# attiny_bo.net
KiCad netlist of a schematic drawn in EAGLE
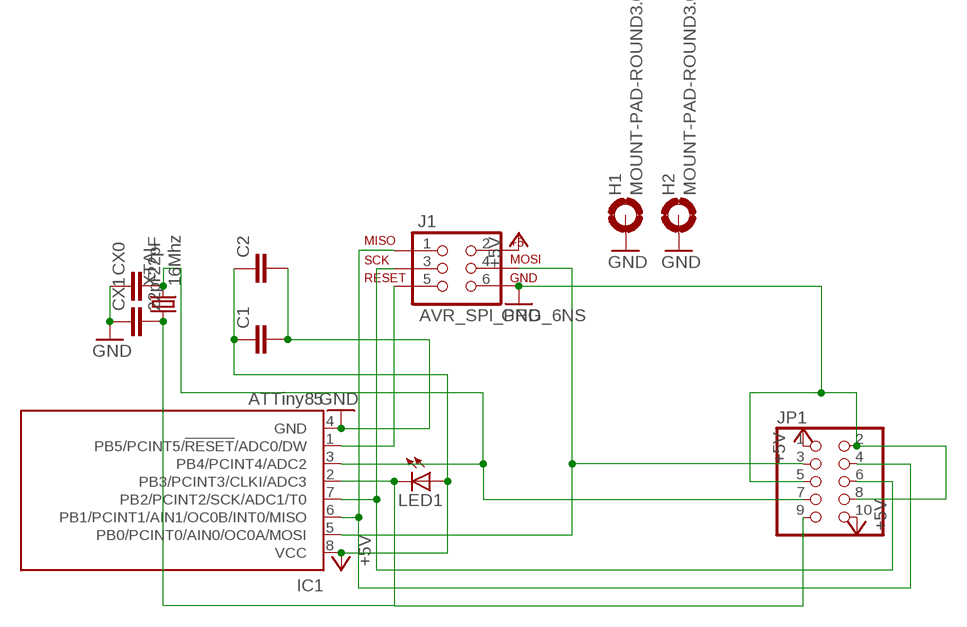
[diagram p0: schematic, sheet 1]

(export (version "E")
  (design (tool "Eeschema 10.0.6"))
  (components
    (comp (ref "C1")
      (value "C-EUC0805")
      (footprint "eagle-import:C0805")
      (libsource (lib "eagle-import") (part "C-EUC0805"))
    )
    (comp (ref "C2")
      (value "C-EUC0805")
      (footprint "eagle-import:C0805")
      (libsource (lib "eagle-import") (part "C-EUC0805"))
    )
    (comp (ref "CX0")
      (value "22pF")
      (footprint "eagle-import:C0603")
      (libsource (lib "eagle-import") (part "C-EUC0603"))
    )
    (comp (ref "CX1")
      (value "22pF")
      (footprint "eagle-import:C0603")
      (libsource (lib "eagle-import") (part "C-EUC0603"))
    )
    (comp (ref "H1")
      (value "MOUNT-PAD-ROUND3.0")
      (footprint "eagle-import:3,0-PAD")
      (libsource (lib "eagle-import") (part "MOUNT-PAD-ROUND3.0"))
    )
    (comp (ref "H2")
      (value "MOUNT-PAD-ROUND3.0")
      (footprint "eagle-import:3,0-PAD")
      (libsource (lib "eagle-import") (part "MOUNT-PAD-ROUND3.0"))
    )
    (comp (ref "IC1")
      (value "ATTiny85")
      (footprint "eagle-import:8S2")
      (fields (field (name "MPN") "ATTINY13-20SU"))
      (libsource (lib "eagle-import") (part "TINY13SU-20"))
    )
    (comp (ref "J1")
      (value "AVR_SPI_PRG_6NS")
      (footprint "eagle-import:2X3-NS")
      (libsource (lib "eagle-import") (part "AVR_SPI_PRG_6NS"))
    )
    (comp (ref "JP1")
      (value "PINHD-2X5")
      (footprint "eagle-import:2X05")
      (libsource (lib "eagle-import") (part "PINHD-2X5"))
    )
    (comp (ref "LED1")
      (value "LED0603")
      (footprint "eagle-import:LED-0603")
      (libsource (lib "eagle-import") (part "LED0603"))
    )
    (comp (ref "XTAL")
      (value "16Mhz")
      (footprint "eagle-import:CTS406")
      (libsource (lib "eagle-import") (part "CRYSTALCTS406"))
    )
  )
  (nets
    (net (code "1") (name "+5V") (class "Default")
      (node (ref "C1") (pin "1") (pinfunction "1_1") (pintype "passive"))
      (node (ref "C2") (pin "1") (pinfunction "1_1") (pintype "passive"))
      (node (ref "IC1") (pin "8") (pinfunction "VCC_8") (pintype "power_in"))
      (node (ref "J1") (pin "2") (pinfunction "2_2") (pintype "passive"))
      (node (ref "JP1") (pin "1") (pinfunction "1_1") (pintype "passive"))
      (node (ref "JP1") (pin "10") (pinfunction "10_10") (pintype "passive"))
      (node (ref "LED1") (pin "A") (pinfunction "A_A") (pintype "passive"))
    )
    (net (code "2") (name "GND") (class "Default")
      (node (ref "C1") (pin "2") (pinfunction "2_2") (pintype "passive"))
      (node (ref "C2") (pin "2") (pinfunction "2_2") (pintype "passive"))
      (node (ref "CX0") (pin "1") (pinfunction "1_1") (pintype "passive"))
      (node (ref "CX1") (pin "1") (pinfunction "1_1") (pintype "passive"))
      (node (ref "H1") (pin "B3,0") (pinfunction "MOUNT_B3,0") (pintype "passive"))
      (node (ref "H2") (pin "B3,0") (pinfunction "MOUNT_B3,0") (pintype "passive"))
      (node (ref "IC1") (pin "4") (pinfunction "GND_4") (pintype "power_in"))
      (node (ref "J1") (pin "6") (pinfunction "6_6") (pintype "passive"))
      (node (ref "JP1") (pin "2") (pinfunction "2_2") (pintype "passive"))
      (node (ref "JP1") (pin "5") (pinfunction "5_5") (pintype "passive"))
      (node (ref "JP1") (pin "8") (pinfunction "8_8") (pintype "passive"))
    )
    (net (code "3") (name "Net-(IC1-PB0{slash}PCINT0{slash}AIN0{slash}OC0A{slash}MOSI)") (class "Default")
      (node (ref "IC1") (pin "5") (pinfunction "PB0/PCINT0/AIN0/OC0A/MOSI_5") (pintype "bidirectional"))
      (node (ref "J1") (pin "4") (pinfunction "4_4") (pintype "passive"))
      (node (ref "JP1") (pin "3") (pinfunction "3_3") (pintype "passive"))
    )
    (net (code "4") (name "Net-(IC1-PB1{slash}PCINT1{slash}AIN1{slash}OC0B{slash}INT0{slash}MISO)") (class "Default")
      (node (ref "IC1") (pin "6") (pinfunction "PB1/PCINT1/AIN1/OC0B/INT0/MISO_6") (pintype "bidirectional"))
      (node (ref "J1") (pin "1") (pinfunction "1_1") (pintype "passive"))
      (node (ref "JP1") (pin "4") (pinfunction "4_4") (pintype "passive"))
    )
    (net (code "5") (name "Net-(IC1-PB2{slash}PCINT2{slash}SCK{slash}ADC1{slash}T0)") (class "Default")
      (node (ref "IC1") (pin "7") (pinfunction "PB2/PCINT2/SCK/ADC1/T0_7") (pintype "bidirectional"))
      (node (ref "J1") (pin "3") (pinfunction "3_3") (pintype "passive"))
      (node (ref "JP1") (pin "6") (pinfunction "6_6") (pintype "passive"))
    )
    (net (code "6") (name "Net-(IC1-PB3{slash}PCINT3{slash}CLKI{slash}ADC3)") (class "Default")
      (node (ref "CX1") (pin "2") (pinfunction "2_2") (pintype "passive"))
      (node (ref "IC1") (pin "2") (pinfunction "PB3/PCINT3/CLKI/ADC3_2") (pintype "bidirectional"))
      (node (ref "JP1") (pin "9") (pinfunction "9_9") (pintype "passive"))
      (node (ref "LED1") (pin "C") (pinfunction "C_C") (pintype "passive"))
      (node (ref "XTAL") (pin "1") (pinfunction "1_1") (pintype "passive"))
    )
    (net (code "7") (name "Net-(IC1-PB4{slash}PCINT4{slash}ADC2)") (class "Default")
      (node (ref "CX0") (pin "2") (pinfunction "2_2") (pintype "passive"))
      (node (ref "IC1") (pin "3") (pinfunction "PB4/PCINT4/ADC2_3") (pintype "bidirectional"))
      (node (ref "JP1") (pin "7") (pinfunction "7_7") (pintype "passive"))
      (node (ref "XTAL") (pin "3") (pinfunction "2_3") (pintype "passive"))
    )
    (net (code "8") (name "Net-(IC1-PB5{slash}PCINT5{slash}~{RESET}{slash}ADC0{slash}DW)") (class "Default")
      (node (ref "IC1") (pin "1") (pinfunction "PB5/PCINT5/~{RESET}/ADC0/DW_1") (pintype "bidirectional"))
      (node (ref "J1") (pin "5") (pinfunction "5_5") (pintype "passive"))
    )
  )
)
